# 3.net
KiCad netlist of a schematic drawn in EAGLE
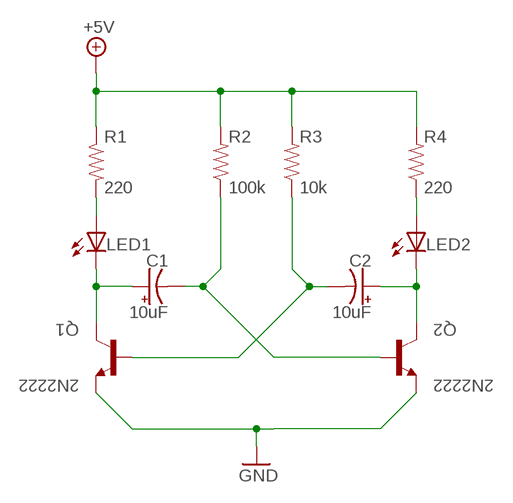
[diagram p0: schematic, sheet 1]

(export (version "E")
  (design (tool "Eeschema 10.0.6"))
  (components
    (comp (ref "C1")
      (value "10uF")
      (footprint "eagle-import:CPOL-RADIAL-2.5MM-5MM")
      (libsource (lib "eagle-import") (part "10UF-POLAR-RADIAL-2.5MM-25V-20%"))
    )
    (comp (ref "C2")
      (value "10uF")
      (footprint "eagle-import:CPOL-RADIAL-2.5MM-5MM")
      (libsource (lib "eagle-import") (part "10UF-POLAR-RADIAL-2.5MM-25V-20%"))
    )
    (comp (ref "LED1")
      (value "LED5MM")
      (footprint "eagle-import:LED5MM")
      (libsource (lib "eagle-import") (part "LED5MM"))
    )
    (comp (ref "LED2")
      (value "LED5MM")
      (footprint "eagle-import:LED5MM")
      (libsource (lib "eagle-import") (part "LED5MM"))
    )
    (comp (ref "Q1")
      (value "2N2222")
      (footprint "eagle-import:TO92-EBC-OVAL")
      (libsource (lib "eagle-import") (part "2N2222"))
    )
    (comp (ref "Q2")
      (value "2N2222")
      (footprint "eagle-import:TO92-EBC-OVAL")
      (libsource (lib "eagle-import") (part "2N2222"))
    )
    (comp (ref "R1")
      (value "220")
      (footprint "eagle-import:AXIAL-0.3")
      (libsource (lib "eagle-import") (part "100OHM-HORIZ-1/4W-1%"))
    )
    (comp (ref "R2")
      (value "100k")
      (footprint "eagle-import:AXIAL-0.3")
      (libsource (lib "eagle-import") (part "100OHM-HORIZ-1/4W-1%"))
    )
    (comp (ref "R3")
      (value "10k")
      (footprint "eagle-import:AXIAL-0.3")
      (libsource (lib "eagle-import") (part "100OHM-HORIZ-1/4W-1%"))
    )
    (comp (ref "R4")
      (value "220")
      (footprint "eagle-import:AXIAL-0.3")
      (libsource (lib "eagle-import") (part "100OHM-HORIZ-1/4W-1%"))
    )
  )
  (nets
    (net (code "1") (name "+5V") (class "Default")
      (node (ref "R1") (pin "P$1") (pinfunction "1_P$1") (pintype "passive"))
      (node (ref "R2") (pin "P$2") (pinfunction "2_P$2") (pintype "passive"))
      (node (ref "R3") (pin "P$2") (pinfunction "2_P$2") (pintype "passive"))
      (node (ref "R4") (pin "P$2") (pinfunction "2_P$2") (pintype "passive"))
    )
    (net (code "2") (name "GND") (class "Default")
      (node (ref "Q1") (pin "E") (pinfunction "E_E") (pintype "passive"))
      (node (ref "Q2") (pin "E") (pinfunction "E_E") (pintype "passive"))
    )
    (net (code "3") (name "Net-(C1-+)") (class "Default")
      (node (ref "C1") (pin "1") (pinfunction "+_1") (pintype "passive"))
      (node (ref "LED1") (pin "K") (pinfunction "C_K") (pintype "passive"))
      (node (ref "Q1") (pin "C") (pinfunction "C_C") (pintype "passive"))
    )
    (net (code "4") (name "Net-(C1--)") (class "Default")
      (node (ref "C1") (pin "2") (pinfunction "-_2") (pintype "passive"))
      (node (ref "Q2") (pin "B") (pinfunction "B_B") (pintype "passive"))
      (node (ref "R2") (pin "P$1") (pinfunction "1_P$1") (pintype "passive"))
    )
    (net (code "5") (name "Net-(C2-+)") (class "Default")
      (node (ref "C2") (pin "1") (pinfunction "+_1") (pintype "passive"))
      (node (ref "LED2") (pin "K") (pinfunction "C_K") (pintype "passive"))
      (node (ref "Q2") (pin "C") (pinfunction "C_C") (pintype "passive"))
    )
    (net (code "6") (name "Net-(C2--)") (class "Default")
      (node (ref "C2") (pin "2") (pinfunction "-_2") (pintype "passive"))
      (node (ref "Q1") (pin "B") (pinfunction "B_B") (pintype "passive"))
      (node (ref "R3") (pin "P$1") (pinfunction "1_P$1") (pintype "passive"))
    )
    (net (code "7") (name "Net-(R1-2)") (class "Default")
      (node (ref "LED1") (pin "A") (pinfunction "A_A") (pintype "passive"))
      (node (ref "R1") (pin "P$2") (pinfunction "2_P$2") (pintype "passive"))
    )
    (net (code "8") (name "Net-(R4-1)") (class "Default")
      (node (ref "LED2") (pin "A") (pinfunction "A_A") (pintype "passive"))
      (node (ref "R4") (pin "P$1") (pinfunction "1_P$1") (pintype "passive"))
    )
  )
)
